# CoilX.net
KiCad netlist of a schematic drawn in EAGLE
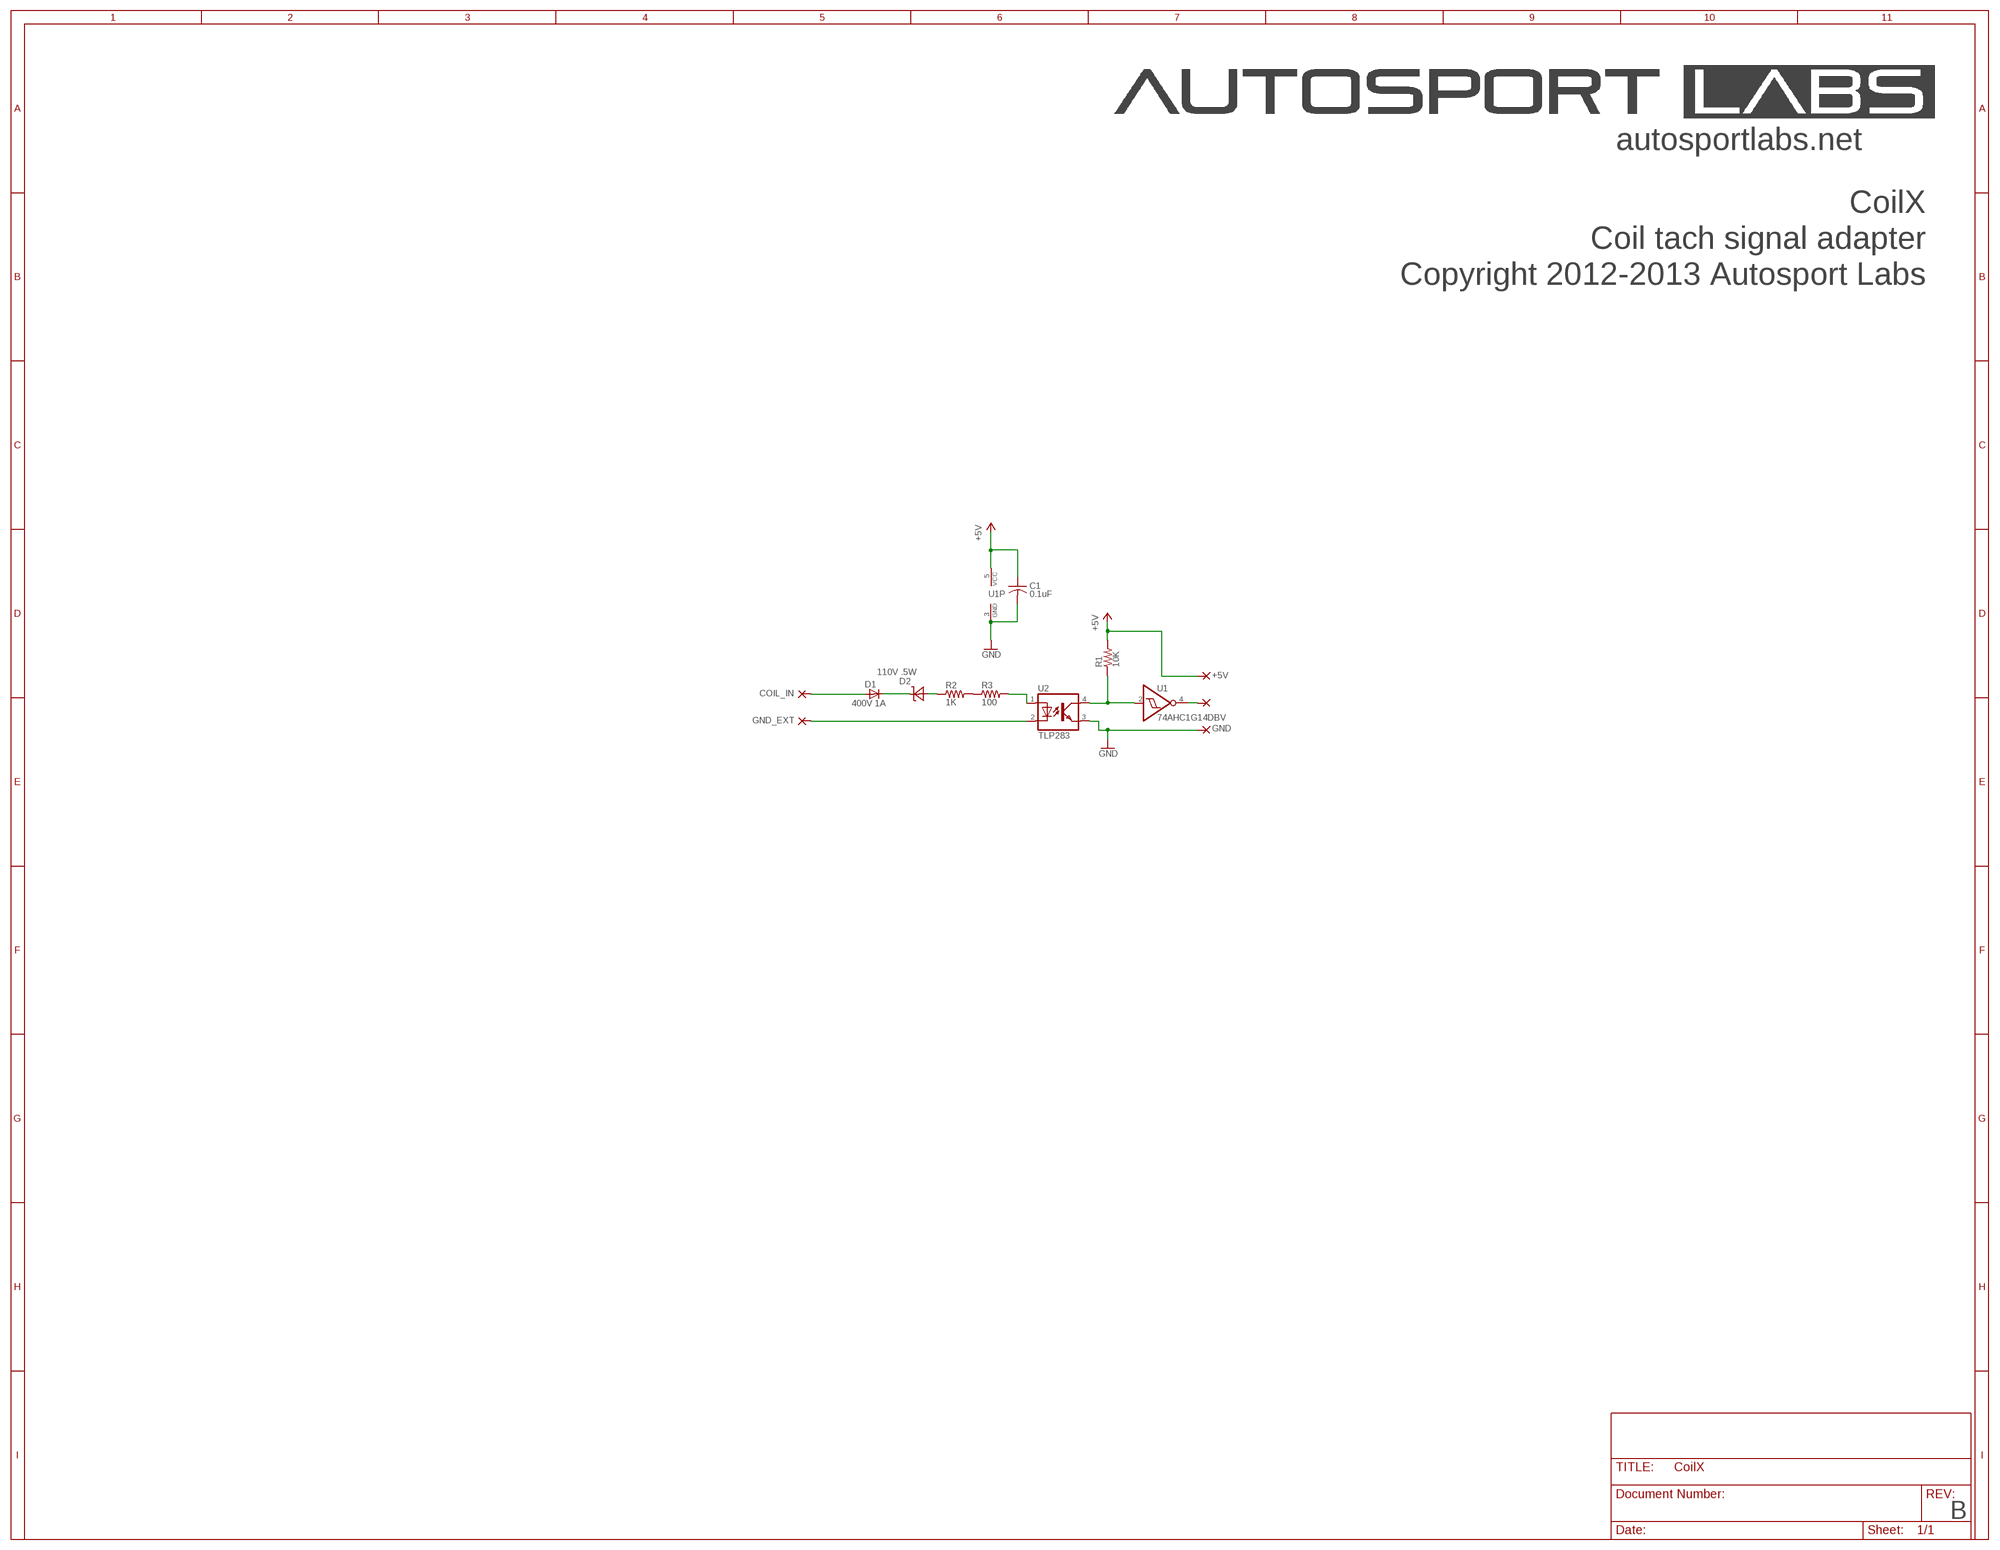
[diagram p0: schematic, sheet 1]

(export (version "E")
  (design (tool "Eeschema 10.0.6"))
  (components
    (comp (ref "+5V")
      (value "WIREPAD3,17/1,2")
      (footprint "eagle-import:3,17_1,2")
      (libsource (lib "eagle-import") (part "WIREPAD3,17/1,2"))
    )
    (comp (ref "C1")
      (value "0.1uF")
      (footprint "eagle-import:C0603")
      (libsource (lib "eagle-import") (part "C-USC0603"))
    )
    (comp (ref "COIL")
      (value "WIREPAD3,17/1,2")
      (footprint "eagle-import:3,17_1,2")
      (libsource (lib "eagle-import") (part "WIREPAD3,17/1,2"))
    )
    (comp (ref "D1")
      (value "400V 1A")
      (footprint "eagle-import:SMA")
      (libsource (lib "eagle-import") (part "DIODE1"))
    )
    (comp (ref "D2")
      (value "110V .5W")
      (footprint "eagle-import:SOD123")
      (libsource (lib "eagle-import") (part "ZENER2"))
    )
    (comp (ref "GND")
      (value "WIREPAD3,17/1,2")
      (footprint "eagle-import:3,17_1,2")
      (libsource (lib "eagle-import") (part "WIREPAD3,17/1,2"))
    )
    (comp (ref "GND_EXT")
      (value "WIREPAD3,17/1,2")
      (footprint "eagle-import:3,17_1,2")
      (libsource (lib "eagle-import") (part "WIREPAD3,17/1,2"))
    )
    (comp (ref "OUT")
      (value "WIREPAD3,17/1,2")
      (footprint "eagle-import:3,17_1,2")
      (libsource (lib "eagle-import") (part "WIREPAD3,17/1,2"))
    )
    (comp (ref "R1")
      (value "10K")
      (footprint "eagle-import:R0603")
      (libsource (lib "eagle-import") (part "R-US_R0603"))
    )
    (comp (ref "R2")
      (value "1K")
      (footprint "eagle-import:R1206")
      (libsource (lib "eagle-import") (part "R-US_R1206"))
    )
    (comp (ref "R3")
      (value "100")
      (footprint "eagle-import:R0603")
      (libsource (lib "eagle-import") (part "R-US_R0603"))
    )
    (comp (ref "U1")
      (value "74AHC1G14DBV")
      (footprint "eagle-import:SOT23-5")
      (libsource (lib "eagle-import") (part "741G14DBVAHC"))
    )
    (comp (ref "U2")
      (value "TLP283")
      (footprint "eagle-import:MINI-FLAT-4")
      (libsource (lib "eagle-import") (part "TLP283"))
    )
  )
  (nets
    (net (code "1") (name "+5V") (class "Default")
      (node (ref "+5V") (pin "1") (pinfunction "P_1") (pintype "passive"))
      (node (ref "C1") (pin "1") (pinfunction "1_1") (pintype "passive"))
      (node (ref "R1") (pin "2") (pinfunction "2_2") (pintype "passive"))
      (node (ref "U1") (pin "5") (pinfunction "VCC_5") (pintype "power_in"))
    )
    (net (code "2") (name "/COIL_IN") (class "Default")
      (node (ref "COIL") (pin "1") (pinfunction "P_1") (pintype "passive"))
      (node (ref "D1") (pin "A") (pinfunction "A_A") (pintype "passive"))
    )
    (net (code "3") (name "/GND_EXT") (class "Default")
      (node (ref "GND_EXT") (pin "1") (pinfunction "P_1") (pintype "passive"))
      (node (ref "U2") (pin "2") (pinfunction "C_2") (pintype "passive"))
    )
    (net (code "4") (name "GND") (class "Default")
      (node (ref "C1") (pin "2") (pinfunction "2_2") (pintype "passive"))
      (node (ref "GND") (pin "1") (pinfunction "P_1") (pintype "passive"))
      (node (ref "U1") (pin "3") (pinfunction "GND_3") (pintype "power_in"))
      (node (ref "U2") (pin "3") (pinfunction "EMIT_3") (pintype "passive"))
    )
    (net (code "5") (name "Net-(D1-PadC)") (class "Default")
      (node (ref "D1") (pin "C") (pinfunction "C_C") (pintype "passive"))
      (node (ref "D2") (pin "C") (pinfunction "C_C") (pintype "passive"))
    )
    (net (code "6") (name "Net-(D2-PadA)") (class "Default")
      (node (ref "D2") (pin "A") (pinfunction "A_A") (pintype "passive"))
      (node (ref "R2") (pin "1") (pinfunction "1_1") (pintype "passive"))
    )
    (net (code "7") (name "Net-(OUT-P)") (class "Default")
      (node (ref "OUT") (pin "1") (pinfunction "P_1") (pintype "passive"))
      (node (ref "U1") (pin "4") (pinfunction "O_4") (pintype "output"))
    )
    (net (code "8") (name "Net-(R2-Pad2)") (class "Default")
      (node (ref "R2") (pin "2") (pinfunction "2_2") (pintype "passive"))
      (node (ref "R3") (pin "1") (pinfunction "1_1") (pintype "passive"))
    )
    (net (code "9") (name "Net-(U1A-I)") (class "Default")
      (node (ref "R1") (pin "1") (pinfunction "1_1") (pintype "passive"))
      (node (ref "U1") (pin "2") (pinfunction "I_2") (pintype "input"))
      (node (ref "U2") (pin "4") (pinfunction "COL_4") (pintype "passive"))
    )
    (net (code "10") (name "Net-(U2-A)") (class "Default")
      (node (ref "R3") (pin "2") (pinfunction "2_2") (pintype "passive"))
      (node (ref "U2") (pin "1") (pinfunction "A_1") (pintype "passive"))
    )
  )
)
